# CONNECTS.net
KiCad netlist of a schematic drawn in Altium Designer
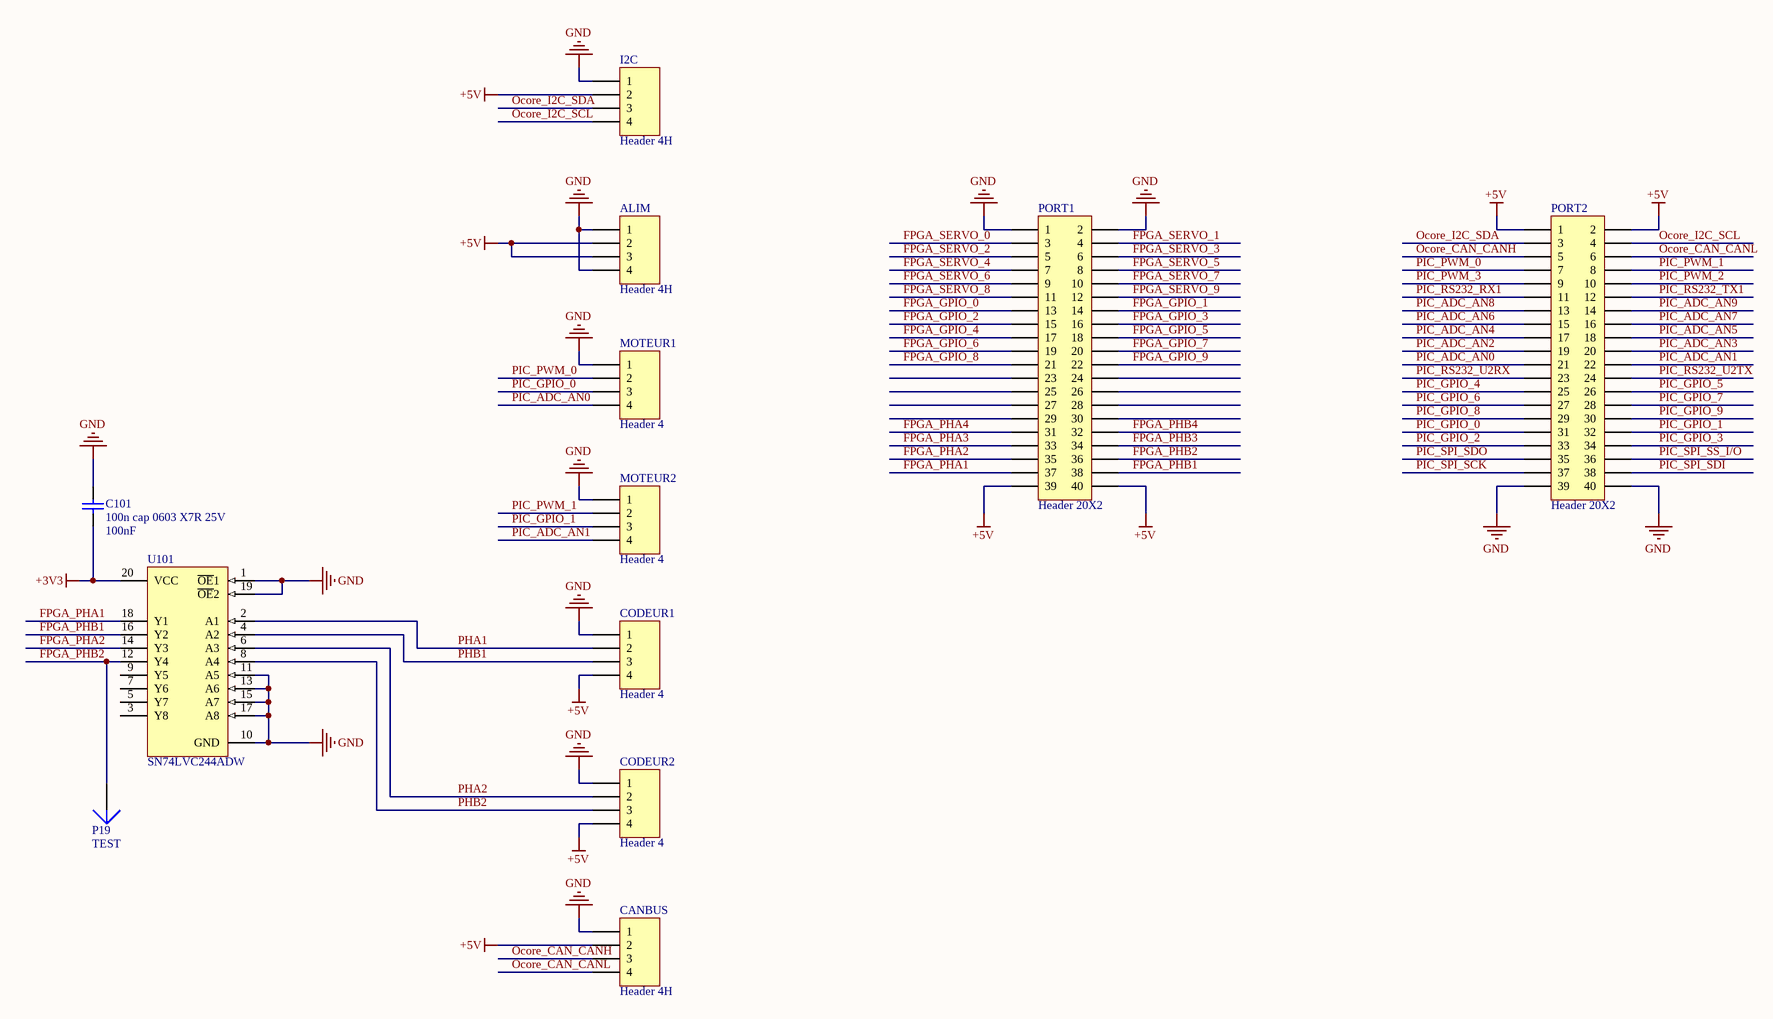
[diagram p0: CONNECTS.SchDoc]

(export (version "E")
  (design (tool "Eeschema 10.0.6"))
  (components
    (comp (ref "ALIM")
      (value "Header 4H")
      (footprint "HDR1X4H")
      (description "Header, 4-Pin, Right Angle")
      (fields (field (name "PUBLISHER") "Altium Limited"))
      (libsource (lib "Miscellaneous Connectors") (part "Header 4H"))
    )
    (comp (ref "C101")
      (value "100n cap 0603 X7R 25V")
      (footprint "1608[0603]")
      (description "Capacitor")
      (fields (field (name "ALTIUM_VALUE") "100nF") (field (name "PUBLISHER") "Altium Limited"))
      (libsource (lib "Miscellaneous Devices") (part "Cap"))
    )
    (comp (ref "CANBUS")
      (value "Header 4H")
      (footprint "HDR1X4H")
      (description "Header, 4-Pin, Right Angle")
      (fields (field (name "PUBLISHER") "Altium Limited"))
      (libsource (lib "Miscellaneous Connectors") (part "Header 4H"))
    )
    (comp (ref "CODEUR1")
      (value "Header 4")
      (footprint "HDR1X4")
      (description "Header, 4-Pin")
      (fields (field (name "PUBLISHER") "Altium Limited"))
      (libsource (lib "Miscellaneous Connectors") (part "Header 4"))
    )
    (comp (ref "CODEUR2")
      (value "Header 4")
      (footprint "HDR1X4")
      (description "Header, 4-Pin")
      (fields (field (name "PUBLISHER") "Altium Limited"))
      (libsource (lib "Miscellaneous Connectors") (part "Header 4"))
    )
    (comp (ref "I2C")
      (value "Header 4H")
      (footprint "HDR1X4H")
      (description "Header, 4-Pin, Right Angle")
      (fields (field (name "PUBLISHER") "Altium Limited"))
      (libsource (lib "Miscellaneous Connectors") (part "Header 4H"))
    )
    (comp (ref "MOTEUR1")
      (value "Header 4")
      (footprint "HDR1X4")
      (description "Header, 4-Pin")
      (fields (field (name "PUBLISHER") "Altium Limited"))
      (libsource (lib "Miscellaneous Connectors") (part "Header 4"))
    )
    (comp (ref "MOTEUR2")
      (value "Header 4")
      (footprint "HDR1X4")
      (description "Header, 4-Pin")
      (fields (field (name "PUBLISHER") "Altium Limited"))
      (libsource (lib "Miscellaneous Connectors") (part "Header 4"))
    )
    (comp (ref "P19")
      (value "TEST")
      (footprint "TP1")
      (description "Plug")
      (fields (field (name "PUBLISHER") "Altium Limited"))
      (libsource (lib "Miscellaneous Connectors") (part "Plug"))
    )
    (comp (ref "PORT1")
      (value "Header 20X2")
      (footprint "HDR2X20")
      (description "Header, 20-Pin, Dual row")
      (fields (field (name "PUBLISHER") "Altium Limited"))
      (libsource (lib "Miscellaneous Connectors") (part "Header 20X2"))
    )
    (comp (ref "PORT2")
      (value "Header 20X2")
      (footprint "HDR2X20")
      (description "Header, 20-Pin, Dual row")
      (fields (field (name "PUBLISHER") "Altium Limited"))
      (libsource (lib "Miscellaneous Connectors") (part "Header 20X2"))
    )
    (comp (ref "U101")
      (value "SN74LVC244ADW")
      (footprint "DW020_N")
      (description "Octal Buffer/Driver with 3-State Outputs")
      (fields (field (name "PUBLISHER") "Altium Limited"))
      (libsource (lib "TI Logic Buffer Line Driver") (part "SN74LVC244ADW"))
    )
  )
  (nets
    (net (code "1") (name "+3V3") (class "Default")
      (node (ref "C101") (pin "1") (pinfunction "1_1") (pintype "passive"))
      (node (ref "U101") (pin "20") (pinfunction "VCC_20") (pintype "power_in"))
    )
    (net (code "2") (name "+5V") (class "Default")
      (node (ref "ALIM") (pin "2") (pinfunction "2_2") (pintype "passive"))
      (node (ref "ALIM") (pin "3") (pinfunction "3_3") (pintype "passive"))
      (node (ref "CANBUS") (pin "2") (pinfunction "2_2") (pintype "passive"))
      (node (ref "CODEUR1") (pin "4") (pinfunction "4_4") (pintype "passive"))
      (node (ref "CODEUR2") (pin "4") (pinfunction "4_4") (pintype "passive"))
      (node (ref "I2C") (pin "2") (pinfunction "2_2") (pintype "passive"))
      (node (ref "PORT1") (pin "39") (pinfunction "39_39") (pintype "passive"))
      (node (ref "PORT1") (pin "40") (pinfunction "40_40") (pintype "passive"))
      (node (ref "PORT2") (pin "1") (pinfunction "1_1") (pintype "passive"))
      (node (ref "PORT2") (pin "2") (pinfunction "2_2") (pintype "passive"))
    )
    (net (code "3") (name "/FPGA_GPIO_0") (class "Default")
      (node (ref "PORT1") (pin "13") (pinfunction "13_13") (pintype "passive"))
    )
    (net (code "4") (name "/FPGA_GPIO_1") (class "Default")
      (node (ref "PORT1") (pin "14") (pinfunction "14_14") (pintype "passive"))
    )
    (net (code "5") (name "/FPGA_GPIO_2") (class "Default")
      (node (ref "PORT1") (pin "15") (pinfunction "15_15") (pintype "passive"))
    )
    (net (code "6") (name "/FPGA_GPIO_3") (class "Default")
      (node (ref "PORT1") (pin "16") (pinfunction "16_16") (pintype "passive"))
    )
    (net (code "7") (name "/FPGA_GPIO_4") (class "Default")
      (node (ref "PORT1") (pin "17") (pinfunction "17_17") (pintype "passive"))
    )
    (net (code "8") (name "/FPGA_GPIO_5") (class "Default")
      (node (ref "PORT1") (pin "18") (pinfunction "18_18") (pintype "passive"))
    )
    (net (code "9") (name "/FPGA_GPIO_6") (class "Default")
      (node (ref "PORT1") (pin "19") (pinfunction "19_19") (pintype "passive"))
    )
    (net (code "10") (name "/FPGA_GPIO_7") (class "Default")
      (node (ref "PORT1") (pin "20") (pinfunction "20_20") (pintype "passive"))
    )
    (net (code "11") (name "/FPGA_GPIO_8") (class "Default")
      (node (ref "PORT1") (pin "21") (pinfunction "21_21") (pintype "passive"))
    )
    (net (code "12") (name "/FPGA_GPIO_9") (class "Default")
      (node (ref "PORT1") (pin "22") (pinfunction "22_22") (pintype "passive"))
    )
    (net (code "13") (name "/FPGA_PHA1") (class "Default")
      (node (ref "PORT1") (pin "37") (pinfunction "37_37") (pintype "passive"))
      (node (ref "U101") (pin "18") (pinfunction "Y1_18") (pintype "tri_state"))
    )
    (net (code "14") (name "/FPGA_PHA2") (class "Default")
      (node (ref "PORT1") (pin "35") (pinfunction "35_35") (pintype "passive"))
      (node (ref "U101") (pin "14") (pinfunction "Y3_14") (pintype "tri_state"))
    )
    (net (code "15") (name "/FPGA_PHA3") (class "Default")
      (node (ref "PORT1") (pin "33") (pinfunction "33_33") (pintype "passive"))
    )
    (net (code "16") (name "/FPGA_PHA4") (class "Default")
      (node (ref "PORT1") (pin "31") (pinfunction "31_31") (pintype "passive"))
    )
    (net (code "17") (name "/FPGA_PHB1") (class "Default")
      (node (ref "PORT1") (pin "38") (pinfunction "38_38") (pintype "passive"))
      (node (ref "U101") (pin "16") (pinfunction "Y2_16") (pintype "tri_state"))
    )
    (net (code "18") (name "/FPGA_PHB2") (class "Default")
      (node (ref "P19") (pin "1") (pinfunction "1_1") (pintype "passive"))
      (node (ref "PORT1") (pin "36") (pinfunction "36_36") (pintype "passive"))
      (node (ref "U101") (pin "12") (pinfunction "Y4_12") (pintype "tri_state"))
    )
    (net (code "19") (name "/FPGA_PHB3") (class "Default")
      (node (ref "PORT1") (pin "34") (pinfunction "34_34") (pintype "passive"))
    )
    (net (code "20") (name "/FPGA_PHB4") (class "Default")
      (node (ref "PORT1") (pin "32") (pinfunction "32_32") (pintype "passive"))
    )
    (net (code "21") (name "/FPGA_SERVO_0") (class "Default")
      (node (ref "PORT1") (pin "3") (pinfunction "3_3") (pintype "passive"))
    )
    (net (code "22") (name "/FPGA_SERVO_1") (class "Default")
      (node (ref "PORT1") (pin "4") (pinfunction "4_4") (pintype "passive"))
    )
    (net (code "23") (name "/FPGA_SERVO_2") (class "Default")
      (node (ref "PORT1") (pin "5") (pinfunction "5_5") (pintype "passive"))
    )
    (net (code "24") (name "/FPGA_SERVO_3") (class "Default")
      (node (ref "PORT1") (pin "6") (pinfunction "6_6") (pintype "passive"))
    )
    (net (code "25") (name "/FPGA_SERVO_4") (class "Default")
      (node (ref "PORT1") (pin "7") (pinfunction "7_7") (pintype "passive"))
    )
    (net (code "26") (name "/FPGA_SERVO_5") (class "Default")
      (node (ref "PORT1") (pin "8") (pinfunction "8_8") (pintype "passive"))
    )
    (net (code "27") (name "/FPGA_SERVO_6") (class "Default")
      (node (ref "PORT1") (pin "9") (pinfunction "9_9") (pintype "passive"))
    )
    (net (code "28") (name "/FPGA_SERVO_7") (class "Default")
      (node (ref "PORT1") (pin "10") (pinfunction "10_10") (pintype "passive"))
    )
    (net (code "29") (name "/FPGA_SERVO_8") (class "Default")
      (node (ref "PORT1") (pin "11") (pinfunction "11_11") (pintype "passive"))
    )
    (net (code "30") (name "/FPGA_SERVO_9") (class "Default")
      (node (ref "PORT1") (pin "12") (pinfunction "12_12") (pintype "passive"))
    )
    (net (code "31") (name "/Ocore_CAN_CANH") (class "Default")
      (node (ref "CANBUS") (pin "3") (pinfunction "3_3") (pintype "passive"))
      (node (ref "PORT2") (pin "5") (pinfunction "5_5") (pintype "passive"))
    )
    (net (code "32") (name "/Ocore_CAN_CANL") (class "Default")
      (node (ref "CANBUS") (pin "4") (pinfunction "4_4") (pintype "passive"))
      (node (ref "PORT2") (pin "6") (pinfunction "6_6") (pintype "passive"))
    )
    (net (code "33") (name "/Ocore_I2C_SCL") (class "Default")
      (node (ref "I2C") (pin "4") (pinfunction "4_4") (pintype "passive"))
      (node (ref "PORT2") (pin "4") (pinfunction "4_4") (pintype "passive"))
    )
    (net (code "34") (name "/Ocore_I2C_SDA") (class "Default")
      (node (ref "I2C") (pin "3") (pinfunction "3_3") (pintype "passive"))
      (node (ref "PORT2") (pin "3") (pinfunction "3_3") (pintype "passive"))
    )
    (net (code "35") (name "/PHA1") (class "Default")
      (node (ref "CODEUR1") (pin "2") (pinfunction "2_2") (pintype "passive"))
      (node (ref "U101") (pin "2") (pinfunction "A1_2") (pintype "input"))
    )
    (net (code "36") (name "/PHA2") (class "Default")
      (node (ref "CODEUR2") (pin "2") (pinfunction "2_2") (pintype "passive"))
      (node (ref "U101") (pin "6") (pinfunction "A3_6") (pintype "input"))
    )
    (net (code "37") (name "/PHB1") (class "Default")
      (node (ref "CODEUR1") (pin "3") (pinfunction "3_3") (pintype "passive"))
      (node (ref "U101") (pin "4") (pinfunction "A2_4") (pintype "input"))
    )
    (net (code "38") (name "/PHB2") (class "Default")
      (node (ref "CODEUR2") (pin "3") (pinfunction "3_3") (pintype "passive"))
      (node (ref "U101") (pin "8") (pinfunction "A4_8") (pintype "input"))
    )
    (net (code "39") (name "/PIC_ADC_AN0") (class "Default")
      (node (ref "MOTEUR1") (pin "4") (pinfunction "4_4") (pintype "passive"))
      (node (ref "PORT2") (pin "21") (pinfunction "21_21") (pintype "passive"))
    )
    (net (code "40") (name "/PIC_ADC_AN1") (class "Default")
      (node (ref "MOTEUR2") (pin "4") (pinfunction "4_4") (pintype "passive"))
      (node (ref "PORT2") (pin "22") (pinfunction "22_22") (pintype "passive"))
    )
    (net (code "41") (name "/PIC_ADC_AN2") (class "Default")
      (node (ref "PORT2") (pin "19") (pinfunction "19_19") (pintype "passive"))
    )
    (net (code "42") (name "/PIC_ADC_AN3") (class "Default")
      (node (ref "PORT2") (pin "20") (pinfunction "20_20") (pintype "passive"))
    )
    (net (code "43") (name "/PIC_ADC_AN4") (class "Default")
      (node (ref "PORT2") (pin "17") (pinfunction "17_17") (pintype "passive"))
    )
    (net (code "44") (name "/PIC_ADC_AN5") (class "Default")
      (node (ref "PORT2") (pin "18") (pinfunction "18_18") (pintype "passive"))
    )
    (net (code "45") (name "/PIC_ADC_AN6") (class "Default")
      (node (ref "PORT2") (pin "15") (pinfunction "15_15") (pintype "passive"))
    )
    (net (code "46") (name "/PIC_ADC_AN7") (class "Default")
      (node (ref "PORT2") (pin "16") (pinfunction "16_16") (pintype "passive"))
    )
    (net (code "47") (name "/PIC_ADC_AN8") (class "Default")
      (node (ref "PORT2") (pin "13") (pinfunction "13_13") (pintype "passive"))
    )
    (net (code "48") (name "/PIC_ADC_AN9") (class "Default")
      (node (ref "PORT2") (pin "14") (pinfunction "14_14") (pintype "passive"))
    )
    (net (code "49") (name "/PIC_GPIO_0") (class "Default")
      (node (ref "MOTEUR1") (pin "3") (pinfunction "3_3") (pintype "passive"))
      (node (ref "PORT2") (pin "31") (pinfunction "31_31") (pintype "passive"))
    )
    (net (code "50") (name "/PIC_GPIO_1") (class "Default")
      (node (ref "MOTEUR2") (pin "3") (pinfunction "3_3") (pintype "passive"))
      (node (ref "PORT2") (pin "32") (pinfunction "32_32") (pintype "passive"))
    )
    (net (code "51") (name "/PIC_GPIO_2") (class "Default")
      (node (ref "PORT2") (pin "33") (pinfunction "33_33") (pintype "passive"))
    )
    (net (code "52") (name "/PIC_GPIO_3") (class "Default")
      (node (ref "PORT2") (pin "34") (pinfunction "34_34") (pintype "passive"))
    )
    (net (code "53") (name "/PIC_GPIO_4") (class "Default")
      (node (ref "PORT2") (pin "25") (pinfunction "25_25") (pintype "passive"))
    )
    (net (code "54") (name "/PIC_GPIO_5") (class "Default")
      (node (ref "PORT2") (pin "26") (pinfunction "26_26") (pintype "passive"))
    )
    (net (code "55") (name "/PIC_GPIO_6") (class "Default")
      (node (ref "PORT2") (pin "27") (pinfunction "27_27") (pintype "passive"))
    )
    (net (code "56") (name "/PIC_GPIO_7") (class "Default")
      (node (ref "PORT2") (pin "28") (pinfunction "28_28") (pintype "passive"))
    )
    (net (code "57") (name "/PIC_GPIO_8") (class "Default")
      (node (ref "PORT2") (pin "29") (pinfunction "29_29") (pintype "passive"))
    )
    (net (code "58") (name "/PIC_GPIO_9") (class "Default")
      (node (ref "PORT2") (pin "30") (pinfunction "30_30") (pintype "passive"))
    )
    (net (code "59") (name "/PIC_PWM_0") (class "Default")
      (node (ref "MOTEUR1") (pin "2") (pinfunction "2_2") (pintype "passive"))
      (node (ref "PORT2") (pin "7") (pinfunction "7_7") (pintype "passive"))
    )
    (net (code "60") (name "/PIC_PWM_1") (class "Default")
      (node (ref "MOTEUR2") (pin "2") (pinfunction "2_2") (pintype "passive"))
      (node (ref "PORT2") (pin "8") (pinfunction "8_8") (pintype "passive"))
    )
    (net (code "61") (name "/PIC_PWM_2") (class "Default")
      (node (ref "PORT2") (pin "10") (pinfunction "10_10") (pintype "passive"))
    )
    (net (code "62") (name "/PIC_PWM_3") (class "Default")
      (node (ref "PORT2") (pin "9") (pinfunction "9_9") (pintype "passive"))
    )
    (net (code "63") (name "/PIC_RS232_RX1") (class "Default")
      (node (ref "PORT2") (pin "11") (pinfunction "11_11") (pintype "passive"))
    )
    (net (code "64") (name "/PIC_RS232_TX1") (class "Default")
      (node (ref "PORT2") (pin "12") (pinfunction "12_12") (pintype "passive"))
    )
    (net (code "65") (name "/PIC_RS232_U2RX") (class "Default")
      (node (ref "PORT2") (pin "23") (pinfunction "23_23") (pintype "passive"))
    )
    (net (code "66") (name "/PIC_RS232_U2TX") (class "Default")
      (node (ref "PORT2") (pin "24") (pinfunction "24_24") (pintype "passive"))
    )
    (net (code "67") (name "/PIC_SPI_SCK") (class "Default")
      (node (ref "PORT2") (pin "37") (pinfunction "37_37") (pintype "passive"))
    )
    (net (code "68") (name "/PIC_SPI_SDI") (class "Default")
      (node (ref "PORT2") (pin "38") (pinfunction "38_38") (pintype "passive"))
    )
    (net (code "69") (name "/PIC_SPI_SDO") (class "Default")
      (node (ref "PORT2") (pin "35") (pinfunction "35_35") (pintype "passive"))
    )
    (net (code "70") (name "/PIC_SPI_SS_I{slash}O") (class "Default")
      (node (ref "PORT2") (pin "36") (pinfunction "36_36") (pintype "passive"))
    )
    (net (code "71") (name "GND") (class "Default")
      (node (ref "ALIM") (pin "1") (pinfunction "1_1") (pintype "passive"))
      (node (ref "ALIM") (pin "4") (pinfunction "4_4") (pintype "passive"))
      (node (ref "C101") (pin "2") (pinfunction "2_2") (pintype "passive"))
      (node (ref "CANBUS") (pin "1") (pinfunction "1_1") (pintype "passive"))
      (node (ref "CODEUR1") (pin "1") (pinfunction "1_1") (pintype "passive"))
      (node (ref "CODEUR2") (pin "1") (pinfunction "1_1") (pintype "passive"))
      (node (ref "I2C") (pin "1") (pinfunction "1_1") (pintype "passive"))
      (node (ref "MOTEUR1") (pin "1") (pinfunction "1_1") (pintype "passive"))
      (node (ref "MOTEUR2") (pin "1") (pinfunction "1_1") (pintype "passive"))
      (node (ref "PORT1") (pin "1") (pinfunction "1_1") (pintype "passive"))
      (node (ref "PORT1") (pin "2") (pinfunction "2_2") (pintype "passive"))
      (node (ref "PORT2") (pin "39") (pinfunction "39_39") (pintype "passive"))
      (node (ref "PORT2") (pin "40") (pinfunction "40_40") (pintype "passive"))
      (node (ref "U101") (pin "1") (pinfunction "~{OE}1_1") (pintype "input"))
      (node (ref "U101") (pin "10") (pinfunction "GND_10") (pintype "power_in"))
      (node (ref "U101") (pin "11") (pinfunction "A5_11") (pintype "input"))
      (node (ref "U101") (pin "13") (pinfunction "A6_13") (pintype "input"))
      (node (ref "U101") (pin "15") (pinfunction "A7_15") (pintype "input"))
      (node (ref "U101") (pin "17") (pinfunction "A8_17") (pintype "input"))
      (node (ref "U101") (pin "19") (pinfunction "~{OE}2_19") (pintype "input"))
    )
    (net (code "72") (name "unconnected-(PORT1-Pad23)") (class "Default")
      (node (ref "PORT1") (pin "23") (pinfunction "23_23") (pintype "passive"))
    )
    (net (code "73") (name "unconnected-(PORT1-Pad24)") (class "Default")
      (node (ref "PORT1") (pin "24") (pinfunction "24_24") (pintype "passive"))
    )
    (net (code "74") (name "unconnected-(PORT1-Pad25)") (class "Default")
      (node (ref "PORT1") (pin "25") (pinfunction "25_25") (pintype "passive"))
    )
    (net (code "75") (name "unconnected-(PORT1-Pad26)") (class "Default")
      (node (ref "PORT1") (pin "26") (pinfunction "26_26") (pintype "passive"))
    )
    (net (code "76") (name "unconnected-(PORT1-Pad27)") (class "Default")
      (node (ref "PORT1") (pin "27") (pinfunction "27_27") (pintype "passive"))
    )
    (net (code "77") (name "unconnected-(PORT1-Pad28)") (class "Default")
      (node (ref "PORT1") (pin "28") (pinfunction "28_28") (pintype "passive"))
    )
    (net (code "78") (name "unconnected-(PORT1-Pad29)") (class "Default")
      (node (ref "PORT1") (pin "29") (pinfunction "29_29") (pintype "passive"))
    )
    (net (code "79") (name "unconnected-(PORT1-Pad30)") (class "Default")
      (node (ref "PORT1") (pin "30") (pinfunction "30_30") (pintype "passive"))
    )
    (net (code "80") (name "unconnected-(U101-Y5-Pad9)") (class "Default")
      (node (ref "U101") (pin "9") (pinfunction "Y5_9") (pintype "tri_state"))
    )
    (net (code "81") (name "unconnected-(U101-Y6-Pad7)") (class "Default")
      (node (ref "U101") (pin "7") (pinfunction "Y6_7") (pintype "tri_state"))
    )
    (net (code "82") (name "unconnected-(U101-Y7-Pad5)") (class "Default")
      (node (ref "U101") (pin "5") (pinfunction "Y7_5") (pintype "tri_state"))
    )
    (net (code "83") (name "unconnected-(U101-Y8-Pad3)") (class "Default")
      (node (ref "U101") (pin "3") (pinfunction "Y8_3") (pintype "tri_state"))
    )
  )
)
